# datasette_connector.net
KiCad netlist of a schematic drawn in EAGLE
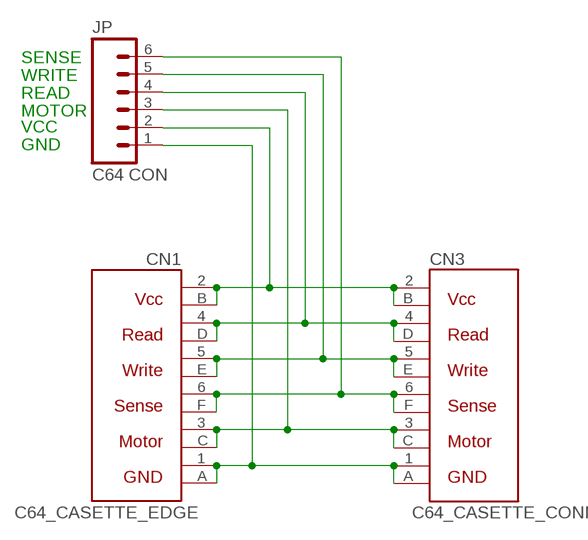
[diagram p0: schematic, sheet 1]

(export (version "E")
  (design (tool "Eeschema 10.0.6"))
  (components
    (comp (ref "CN1")
      (value "C64_CASETTE_EDGE")
      (footprint "eagle-import:C64_CASSETTE")
      (libsource (lib "eagle-import") (part "C64_CASETTE_EDGE"))
    )
    (comp (ref "CN3")
      (value "C64_CASETTE_CONN")
      (footprint "eagle-import:C64_CASSETTE_CONN")
      (libsource (lib "eagle-import") (part "C64_CASETTE_CONN"))
    )
    (comp (ref "JP")
      (value "C64 CON")
      (footprint "eagle-import:1X06_LOCK_LONGPADS")
      (libsource (lib "eagle-import") (part "M06LOCK_LONGPADS"))
    )
  )
  (nets
    (net (code "1") (name "Net-(CN1-GND1)") (class "Default")
      (node (ref "CN1") (pin "1") (pinfunction "GND1_1") (pintype "power_in"))
      (node (ref "CN1") (pin "A") (pinfunction "GND2_A") (pintype "power_in"))
      (node (ref "CN3") (pin "1") (pinfunction "GND1_1") (pintype "passive"))
      (node (ref "CN3") (pin "A") (pinfunction "GND2_A") (pintype "passive"))
      (node (ref "JP") (pin "1") (pinfunction "1_1") (pintype "passive"))
    )
    (net (code "2") (name "Net-(CN1-MOTOR1)") (class "Default")
      (node (ref "CN1") (pin "3") (pinfunction "MOTOR1_3") (pintype "output"))
      (node (ref "CN1") (pin "C") (pinfunction "MOTOR2_C") (pintype "output"))
      (node (ref "CN3") (pin "3") (pinfunction "MOTOR1_3") (pintype "input"))
      (node (ref "CN3") (pin "C") (pinfunction "MOTOR2_C") (pintype "input"))
      (node (ref "JP") (pin "3") (pinfunction "3_3") (pintype "passive"))
    )
    (net (code "3") (name "Net-(CN1-READ1)") (class "Default")
      (node (ref "CN1") (pin "4") (pinfunction "READ1_4") (pintype "output"))
      (node (ref "CN1") (pin "D") (pinfunction "READ2_D") (pintype "output"))
      (node (ref "CN3") (pin "4") (pinfunction "READ1_4") (pintype "output"))
      (node (ref "CN3") (pin "D") (pinfunction "READ2_D") (pintype "passive"))
      (node (ref "JP") (pin "4") (pinfunction "4_4") (pintype "passive"))
    )
    (net (code "4") (name "Net-(CN1-SENSE1)") (class "Default")
      (node (ref "CN1") (pin "6") (pinfunction "SENSE1_6") (pintype "input"))
      (node (ref "CN1") (pin "F") (pinfunction "SENSE2_F") (pintype "input"))
      (node (ref "CN3") (pin "6") (pinfunction "SENSE1_6") (pintype "output"))
      (node (ref "CN3") (pin "F") (pinfunction "SENSE2_F") (pintype "passive"))
      (node (ref "JP") (pin "6") (pinfunction "6_6") (pintype "passive"))
    )
    (net (code "5") (name "Net-(CN1-VCC1)") (class "Default")
      (node (ref "CN1") (pin "2") (pinfunction "VCC1_2") (pintype "power_in"))
      (node (ref "CN1") (pin "B") (pinfunction "VCC2_B") (pintype "power_in"))
      (node (ref "CN3") (pin "2") (pinfunction "VCC1_2") (pintype "passive"))
      (node (ref "CN3") (pin "B") (pinfunction "VCC2_B") (pintype "passive"))
      (node (ref "JP") (pin "2") (pinfunction "2_2") (pintype "passive"))
    )
    (net (code "6") (name "Net-(CN1-WRITE1)") (class "Default")
      (node (ref "CN1") (pin "5") (pinfunction "WRITE1_5") (pintype "input"))
      (node (ref "CN1") (pin "E") (pinfunction "WRITE2_E") (pintype "input"))
      (node (ref "CN3") (pin "5") (pinfunction "WRITE1_5") (pintype "input"))
      (node (ref "CN3") (pin "E") (pinfunction "WRITE2_E") (pintype "input"))
      (node (ref "JP") (pin "5") (pinfunction "5_5") (pintype "passive"))
    )
  )
)
